# MX6ULL_DDR.net
KiCad netlist of a schematic drawn in Altium Designer
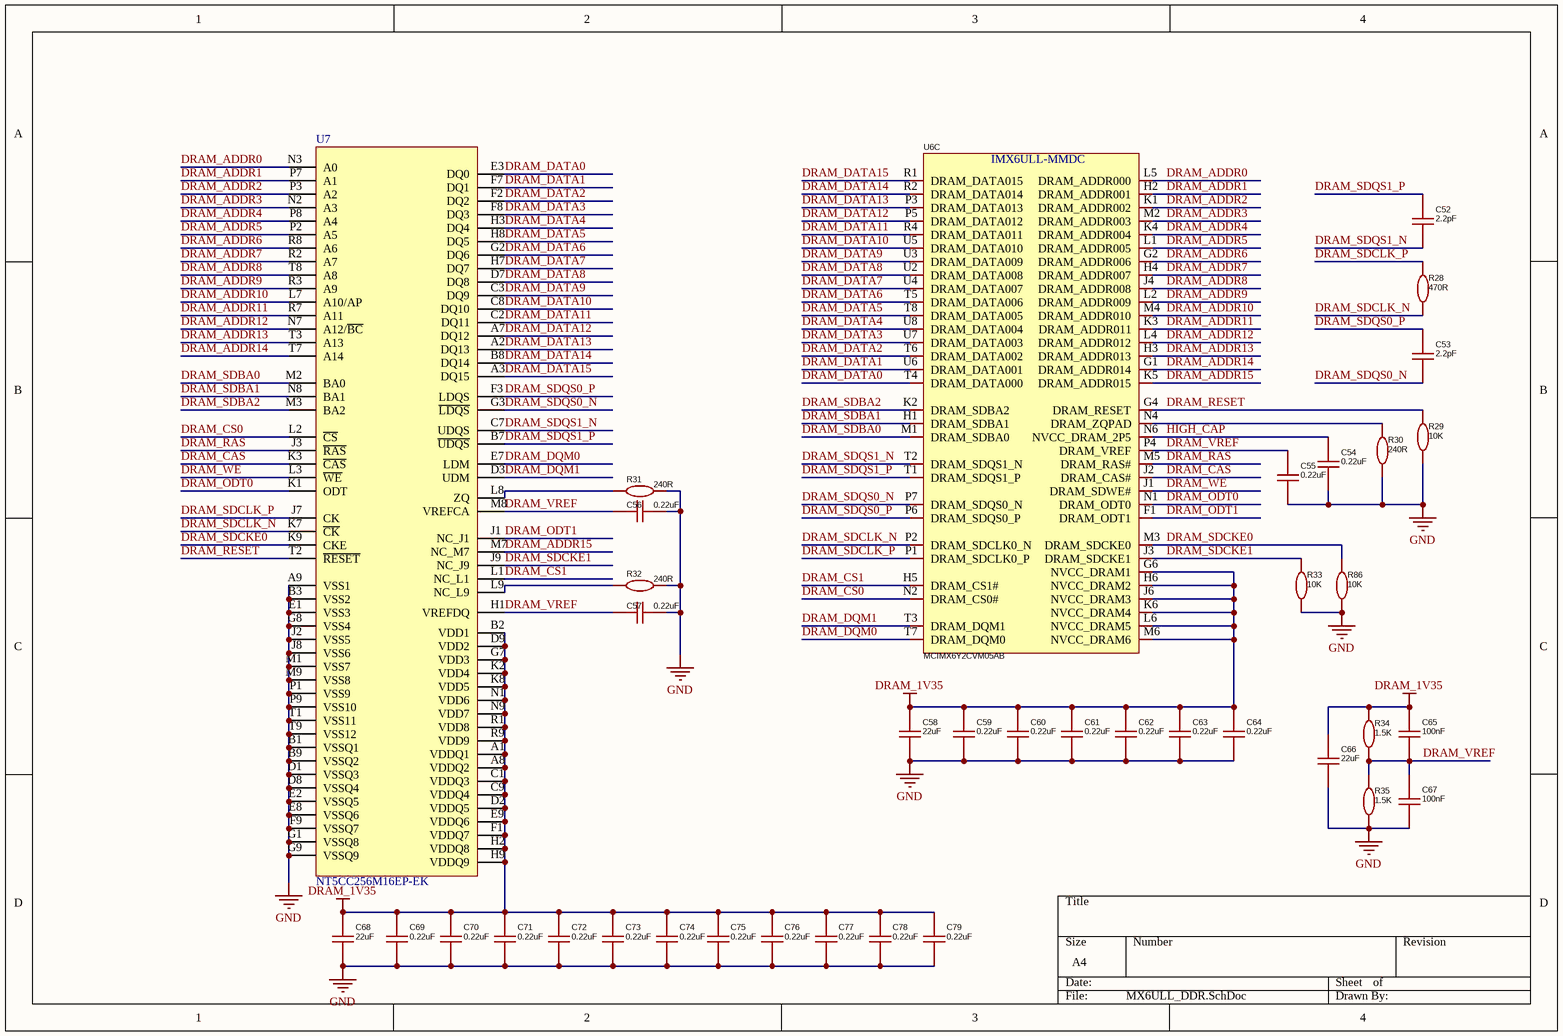
[diagram p0: MX6ULL_DDR.SchDoc]

(export (version "E")
  (design (tool "Eeschema 10.0.6"))
  (components
    (comp (ref "C52")
      (value "2.2pF")
      (footprint "PcbLib1:C0402")
      (description "容值:100nF;精度:±10%;额定电压:50V;材质(温度系数):X7R;")
      (fields
        (field (name "MANUFACTURER") "muRata(村田)")
        (field (name "MANUFACTURER PART") "GRM155R71H104KE14D")
      )
      (libsource (lib "Schlib1") (part "C0402"))
    )
    (comp (ref "C53")
      (value "2.2pF")
      (footprint "PcbLib1:C0402")
      (description "容值:100nF;精度:±10%;额定电压:50V;材质(温度系数):X7R;")
      (fields
        (field (name "MANUFACTURER") "muRata(村田)")
        (field (name "MANUFACTURER PART") "GRM155R71H104KE14D")
      )
      (libsource (lib "Schlib1") (part "C0402"))
    )
    (comp (ref "C54")
      (value "0.22uF")
      (footprint "PcbLib1:C0402")
      (description "容值:100nF;精度:±10%;额定电压:50V;材质(温度系数):X7R;")
      (fields
        (field (name "MANUFACTURER") "muRata(村田)")
        (field (name "MANUFACTURER PART") "GRM155R71H104KE14D")
      )
      (libsource (lib "Schlib1") (part "C0402"))
    )
    (comp (ref "C55")
      (value "0.22uF")
      (footprint "PcbLib1:C0402")
      (description "容值:100nF;精度:±10%;额定电压:50V;材质(温度系数):X7R;")
      (fields
        (field (name "MANUFACTURER") "muRata(村田)")
        (field (name "MANUFACTURER PART") "GRM155R71H104KE14D")
      )
      (libsource (lib "Schlib1") (part "C0402"))
    )
    (comp (ref "C56")
      (value "0.22uF")
      (footprint "PcbLib1:C0402")
      (description "容值:100nF;精度:±10%;额定电压:50V;材质(温度系数):X7R;")
      (fields
        (field (name "MANUFACTURER") "muRata(村田)")
        (field (name "MANUFACTURER PART") "GRM155R71H104KE14D")
      )
      (libsource (lib "Schlib1") (part "C0402"))
    )
    (comp (ref "C57")
      (value "0.22uF")
      (footprint "PcbLib1:C0402")
      (description "容值:100nF;精度:±10%;额定电压:50V;材质(温度系数):X7R;")
      (fields
        (field (name "MANUFACTURER") "muRata(村田)")
        (field (name "MANUFACTURER PART") "GRM155R71H104KE14D")
      )
      (libsource (lib "Schlib1") (part "C0402"))
    )
    (comp (ref "C58")
      (value "22uF")
      (footprint "PcbLib1:C0603")
      (description "容值:22uF;精度:±20%;额定电压:10V;材质(温度系数):X5R;")
      (fields
        (field (name "MANUFACTURER") "Chinocera(华瓷)")
        (field (name "MANUFACTURER PART") "HGC0603R5226M100NTHJ")
      )
      (libsource (lib "Schlib1") (part "C0603"))
    )
    (comp (ref "C59")
      (value "0.22uF")
      (footprint "PcbLib1:C0402")
      (description "容值:100nF;精度:±10%;额定电压:50V;材质(温度系数):X7R;")
      (fields
        (field (name "MANUFACTURER") "muRata(村田)")
        (field (name "MANUFACTURER PART") "GRM155R71H104KE14D")
      )
      (libsource (lib "Schlib1") (part "C0402"))
    )
    (comp (ref "C60")
      (value "0.22uF")
      (footprint "PcbLib1:C0402")
      (description "容值:100nF;精度:±10%;额定电压:50V;材质(温度系数):X7R;")
      (fields
        (field (name "MANUFACTURER") "muRata(村田)")
        (field (name "MANUFACTURER PART") "GRM155R71H104KE14D")
      )
      (libsource (lib "Schlib1") (part "C0402"))
    )
    (comp (ref "C61")
      (value "0.22uF")
      (footprint "PcbLib1:C0402")
      (description "容值:100nF;精度:±10%;额定电压:50V;材质(温度系数):X7R;")
      (fields
        (field (name "MANUFACTURER") "muRata(村田)")
        (field (name "MANUFACTURER PART") "GRM155R71H104KE14D")
      )
      (libsource (lib "Schlib1") (part "C0402"))
    )
    (comp (ref "C62")
      (value "0.22uF")
      (footprint "PcbLib1:C0402")
      (description "容值:100nF;精度:±10%;额定电压:50V;材质(温度系数):X7R;")
      (fields
        (field (name "MANUFACTURER") "muRata(村田)")
        (field (name "MANUFACTURER PART") "GRM155R71H104KE14D")
      )
      (libsource (lib "Schlib1") (part "C0402"))
    )
    (comp (ref "C63")
      (value "0.22uF")
      (footprint "PcbLib1:C0402")
      (description "容值:100nF;精度:±10%;额定电压:50V;材质(温度系数):X7R;")
      (fields
        (field (name "MANUFACTURER") "muRata(村田)")
        (field (name "MANUFACTURER PART") "GRM155R71H104KE14D")
      )
      (libsource (lib "Schlib1") (part "C0402"))
    )
    (comp (ref "C64")
      (value "0.22uF")
      (footprint "PcbLib1:C0402")
      (description "容值:100nF;精度:±10%;额定电压:50V;材质(温度系数):X7R;")
      (fields
        (field (name "MANUFACTURER") "muRata(村田)")
        (field (name "MANUFACTURER PART") "GRM155R71H104KE14D")
      )
      (libsource (lib "Schlib1") (part "C0402"))
    )
    (comp (ref "C65")
      (value "100nF")
      (footprint "PcbLib1:C0402")
      (description "容值:100nF;精度:±10%;额定电压:50V;材质(温度系数):X7R;")
      (fields
        (field (name "MANUFACTURER") "muRata(村田)")
        (field (name "MANUFACTURER PART") "GRM155R71H104KE14D")
      )
      (libsource (lib "Schlib1") (part "C0402"))
    )
    (comp (ref "C66")
      (value "22uF")
      (footprint "PcbLib1:C0603")
      (description "容值:22uF;精度:±20%;额定电压:10V;材质(温度系数):X5R;")
      (fields
        (field (name "MANUFACTURER") "Chinocera(华瓷)")
        (field (name "MANUFACTURER PART") "HGC0603R5226M100NTHJ")
      )
      (libsource (lib "Schlib1") (part "C0603"))
    )
    (comp (ref "C67")
      (value "100nF")
      (footprint "PcbLib1:C0402")
      (description "容值:100nF;精度:±10%;额定电压:50V;材质(温度系数):X7R;")
      (fields
        (field (name "MANUFACTURER") "muRata(村田)")
        (field (name "MANUFACTURER PART") "GRM155R71H104KE14D")
      )
      (libsource (lib "Schlib1") (part "C0402"))
    )
    (comp (ref "C68")
      (value "22uF")
      (footprint "PcbLib1:C0603")
      (description "容值:22uF;精度:±20%;额定电压:10V;材质(温度系数):X5R;")
      (fields
        (field (name "MANUFACTURER") "Chinocera(华瓷)")
        (field (name "MANUFACTURER PART") "HGC0603R5226M100NTHJ")
      )
      (libsource (lib "Schlib1") (part "C0603"))
    )
    (comp (ref "C69")
      (value "0.22uF")
      (footprint "PcbLib1:C0402")
      (description "容值:100nF;精度:±10%;额定电压:50V;材质(温度系数):X7R;")
      (fields
        (field (name "MANUFACTURER") "muRata(村田)")
        (field (name "MANUFACTURER PART") "GRM155R71H104KE14D")
      )
      (libsource (lib "Schlib1") (part "C0402"))
    )
    (comp (ref "C70")
      (value "0.22uF")
      (footprint "PcbLib1:C0402")
      (description "容值:100nF;精度:±10%;额定电压:50V;材质(温度系数):X7R;")
      (fields
        (field (name "MANUFACTURER") "muRata(村田)")
        (field (name "MANUFACTURER PART") "GRM155R71H104KE14D")
      )
      (libsource (lib "Schlib1") (part "C0402"))
    )
    (comp (ref "C71")
      (value "0.22uF")
      (footprint "PcbLib1:C0402")
      (description "容值:100nF;精度:±10%;额定电压:50V;材质(温度系数):X7R;")
      (fields
        (field (name "MANUFACTURER") "muRata(村田)")
        (field (name "MANUFACTURER PART") "GRM155R71H104KE14D")
      )
      (libsource (lib "Schlib1") (part "C0402"))
    )
    (comp (ref "C72")
      (value "0.22uF")
      (footprint "PcbLib1:C0402")
      (description "容值:100nF;精度:±10%;额定电压:50V;材质(温度系数):X7R;")
      (fields
        (field (name "MANUFACTURER") "muRata(村田)")
        (field (name "MANUFACTURER PART") "GRM155R71H104KE14D")
      )
      (libsource (lib "Schlib1") (part "C0402"))
    )
    (comp (ref "C73")
      (value "0.22uF")
      (footprint "PcbLib1:C0402")
      (description "容值:100nF;精度:±10%;额定电压:50V;材质(温度系数):X7R;")
      (fields
        (field (name "MANUFACTURER") "muRata(村田)")
        (field (name "MANUFACTURER PART") "GRM155R71H104KE14D")
      )
      (libsource (lib "Schlib1") (part "C0402"))
    )
    (comp (ref "C74")
      (value "0.22uF")
      (footprint "PcbLib1:C0402")
      (description "容值:100nF;精度:±10%;额定电压:50V;材质(温度系数):X7R;")
      (fields
        (field (name "MANUFACTURER") "muRata(村田)")
        (field (name "MANUFACTURER PART") "GRM155R71H104KE14D")
      )
      (libsource (lib "Schlib1") (part "C0402"))
    )
    (comp (ref "C75")
      (value "0.22uF")
      (footprint "PcbLib1:C0402")
      (description "容值:100nF;精度:±10%;额定电压:50V;材质(温度系数):X7R;")
      (fields
        (field (name "MANUFACTURER") "muRata(村田)")
        (field (name "MANUFACTURER PART") "GRM155R71H104KE14D")
      )
      (libsource (lib "Schlib1") (part "C0402"))
    )
    (comp (ref "C76")
      (value "0.22uF")
      (footprint "PcbLib1:C0402")
      (description "容值:100nF;精度:±10%;额定电压:50V;材质(温度系数):X7R;")
      (fields
        (field (name "MANUFACTURER") "muRata(村田)")
        (field (name "MANUFACTURER PART") "GRM155R71H104KE14D")
      )
      (libsource (lib "Schlib1") (part "C0402"))
    )
    (comp (ref "C77")
      (value "0.22uF")
      (footprint "PcbLib1:C0402")
      (description "容值:100nF;精度:±10%;额定电压:50V;材质(温度系数):X7R;")
      (fields
        (field (name "MANUFACTURER") "muRata(村田)")
        (field (name "MANUFACTURER PART") "GRM155R71H104KE14D")
      )
      (libsource (lib "Schlib1") (part "C0402"))
    )
    (comp (ref "C78")
      (value "0.22uF")
      (footprint "PcbLib1:C0402")
      (description "容值:100nF;精度:±10%;额定电压:50V;材质(温度系数):X7R;")
      (fields
        (field (name "MANUFACTURER") "muRata(村田)")
        (field (name "MANUFACTURER PART") "GRM155R71H104KE14D")
      )
      (libsource (lib "Schlib1") (part "C0402"))
    )
    (comp (ref "C79")
      (value "0.22uF")
      (footprint "PcbLib1:C0402")
      (description "容值:100nF;精度:±10%;额定电压:50V;材质(温度系数):X7R;")
      (fields
        (field (name "MANUFACTURER") "muRata(村田)")
        (field (name "MANUFACTURER PART") "GRM155R71H104KE14D")
      )
      (libsource (lib "Schlib1") (part "C0402"))
    )
    (comp (ref "R28")
      (value "470R")
      (footprint "PcbLib1:R0402")
      (description "电阻类型:厚膜电阻;阻值:1kΩ;精度:±1%;功率:62.5mW;最大工作电压:50V;温度系数:±100ppm/℃;")
      (fields
        (field (name "MANUFACTURER") "UNI-ROYAL(厚声)")
        (field (name "MANUFACTURER PART") "0402WGF1001TCE")
      )
      (libsource (lib "Schlib1") (part "R0402"))
    )
    (comp (ref "R29")
      (value "10K")
      (footprint "PcbLib1:R0402")
      (description "电阻类型:厚膜电阻;阻值:1kΩ;精度:±1%;功率:62.5mW;最大工作电压:50V;温度系数:±100ppm/℃;")
      (fields
        (field (name "MANUFACTURER") "UNI-ROYAL(厚声)")
        (field (name "MANUFACTURER PART") "0402WGF1001TCE")
      )
      (libsource (lib "Schlib1") (part "R0402"))
    )
    (comp (ref "R30")
      (value "240R")
      (footprint "PcbLib1:R0402")
      (description "电阻类型:厚膜电阻;阻值:1kΩ;精度:±1%;功率:62.5mW;最大工作电压:50V;温度系数:±100ppm/℃;")
      (fields
        (field (name "MANUFACTURER") "UNI-ROYAL(厚声)")
        (field (name "MANUFACTURER PART") "0402WGF1001TCE")
      )
      (libsource (lib "Schlib1") (part "R0402"))
    )
    (comp (ref "R31")
      (value "240R")
      (footprint "PcbLib1:R0402")
      (description "电阻类型:厚膜电阻;阻值:1kΩ;精度:±1%;功率:62.5mW;最大工作电压:50V;温度系数:±100ppm/℃;")
      (fields
        (field (name "MANUFACTURER") "UNI-ROYAL(厚声)")
        (field (name "MANUFACTURER PART") "0402WGF1001TCE")
      )
      (libsource (lib "Schlib1") (part "R0402"))
    )
    (comp (ref "R32")
      (value "240R")
      (footprint "PcbLib1:R0402")
      (description "电阻类型:厚膜电阻;阻值:1kΩ;精度:±1%;功率:62.5mW;最大工作电压:50V;温度系数:±100ppm/℃;")
      (fields
        (field (name "MANUFACTURER") "UNI-ROYAL(厚声)")
        (field (name "MANUFACTURER PART") "0402WGF1001TCE")
      )
      (libsource (lib "Schlib1") (part "R0402"))
    )
    (comp (ref "R33")
      (value "10K")
      (footprint "PcbLib1:R0402")
      (description "电阻类型:厚膜电阻;阻值:1kΩ;精度:±1%;功率:62.5mW;最大工作电压:50V;温度系数:±100ppm/℃;")
      (fields
        (field (name "MANUFACTURER") "UNI-ROYAL(厚声)")
        (field (name "MANUFACTURER PART") "0402WGF1001TCE")
      )
      (libsource (lib "Schlib1") (part "R0402"))
    )
    (comp (ref "R34")
      (value "1.5K")
      (footprint "PcbLib1:R0402")
      (description "电阻类型:厚膜电阻;阻值:1kΩ;精度:±1%;功率:62.5mW;最大工作电压:50V;温度系数:±100ppm/℃;")
      (fields
        (field (name "MANUFACTURER") "UNI-ROYAL(厚声)")
        (field (name "MANUFACTURER PART") "0402WGF1001TCE")
      )
      (libsource (lib "Schlib1") (part "R0402"))
    )
    (comp (ref "R35")
      (value "1.5K")
      (footprint "PcbLib1:R0402")
      (description "电阻类型:厚膜电阻;阻值:1kΩ;精度:±1%;功率:62.5mW;最大工作电压:50V;温度系数:±100ppm/℃;")
      (fields
        (field (name "MANUFACTURER") "UNI-ROYAL(厚声)")
        (field (name "MANUFACTURER PART") "0402WGF1001TCE")
      )
      (libsource (lib "Schlib1") (part "R0402"))
    )
    (comp (ref "R86")
      (value "10K")
      (footprint "PcbLib1:R0402")
      (description "电阻类型:厚膜电阻;阻值:1kΩ;精度:±1%;功率:62.5mW;最大工作电压:50V;温度系数:±100ppm/℃;")
      (fields
        (field (name "MANUFACTURER") "UNI-ROYAL(厚声)")
        (field (name "MANUFACTURER PART") "0402WGF1001TCE")
      )
      (libsource (lib "Schlib1") (part "R0402"))
    )
    (comp (ref "U6")
      (value "MCIMX6Y2CVM05AB")
      (footprint "PcbLib1:BGA-289_L14.0-W14.0-R17-C17-P0.80-BL")
      (description "CPU内核:ARM-A系列;RAM总容量:128KB;GPIO端口数量:-;工作电压范围:-;CPU最大主频:528MHz;程序存储器类型:-;应用领域:-;")
      (fields (field (name "MANUFACTURER") "NXP(恩智浦)"))
      (libsource (lib "Schlib1") (part "MCIMX6Y2CVM05AB"))
    )
    (comp (ref "U7")
      (value "NT5CC256M16EP-EK")
      (footprint "PcbLib1:TFBGA-96_L13.0-W8.0-R16-C6-P0.80-TL")
      (libsource (lib "Schlib1") (part "MT41K256M16TW"))
    )
  )
  (nets
    (net (code "1") (name "/DRAM_ADDR0") (class "Default")
      (node (ref "U6") (pin "L5") (pinfunction "DRAM_ADDR000_L5") (pintype "passive"))
      (node (ref "U7") (pin "N3") (pinfunction "A0_N3") (pintype "passive"))
    )
    (net (code "2") (name "/DRAM_ADDR1") (class "Default")
      (node (ref "U6") (pin "H2") (pinfunction "DRAM_ADDR001_H2") (pintype "passive"))
      (node (ref "U7") (pin "P7") (pinfunction "A1_P7") (pintype "passive"))
    )
    (net (code "3") (name "/DRAM_ADDR2") (class "Default")
      (node (ref "U6") (pin "K1") (pinfunction "DRAM_ADDR002_K1") (pintype "passive"))
      (node (ref "U7") (pin "P3") (pinfunction "A2_P3") (pintype "passive"))
    )
    (net (code "4") (name "/DRAM_ADDR3") (class "Default")
      (node (ref "U6") (pin "M2") (pinfunction "DRAM_ADDR003_M2") (pintype "passive"))
      (node (ref "U7") (pin "N2") (pinfunction "A3_N2") (pintype "passive"))
    )
    (net (code "5") (name "/DRAM_ADDR4") (class "Default")
      (node (ref "U6") (pin "K4") (pinfunction "DRAM_ADDR004_K4") (pintype "passive"))
      (node (ref "U7") (pin "P8") (pinfunction "A4_P8") (pintype "passive"))
    )
    (net (code "6") (name "/DRAM_ADDR5") (class "Default")
      (node (ref "U6") (pin "L1") (pinfunction "DRAM_ADDR005_L1") (pintype "passive"))
      (node (ref "U7") (pin "P2") (pinfunction "A5_P2") (pintype "passive"))
    )
    (net (code "7") (name "/DRAM_ADDR6") (class "Default")
      (node (ref "U6") (pin "G2") (pinfunction "DRAM_ADDR006_G2") (pintype "passive"))
      (node (ref "U7") (pin "R8") (pinfunction "A6_R8") (pintype "passive"))
    )
    (net (code "8") (name "/DRAM_ADDR7") (class "Default")
      (node (ref "U6") (pin "H4") (pinfunction "DRAM_ADDR007_H4") (pintype "passive"))
      (node (ref "U7") (pin "R2") (pinfunction "A7_R2") (pintype "passive"))
    )
    (net (code "9") (name "/DRAM_ADDR8") (class "Default")
      (node (ref "U6") (pin "J4") (pinfunction "DRAM_ADDR008_J4") (pintype "passive"))
      (node (ref "U7") (pin "T8") (pinfunction "A8_T8") (pintype "passive"))
    )
    (net (code "10") (name "/DRAM_ADDR9") (class "Default")
      (node (ref "U6") (pin "L2") (pinfunction "DRAM_ADDR009_L2") (pintype "passive"))
      (node (ref "U7") (pin "R3") (pinfunction "A9_R3") (pintype "passive"))
    )
    (net (code "11") (name "/DRAM_ADDR10") (class "Default")
      (node (ref "U6") (pin "M4") (pinfunction "DRAM_ADDR010_M4") (pintype "passive"))
      (node (ref "U7") (pin "L7") (pinfunction "A10/AP_L7") (pintype "passive"))
    )
    (net (code "12") (name "/DRAM_ADDR11") (class "Default")
      (node (ref "U6") (pin "K3") (pinfunction "DRAM_ADDR011_K3") (pintype "passive"))
      (node (ref "U7") (pin "R7") (pinfunction "A11_R7") (pintype "passive"))
    )
    (net (code "13") (name "/DRAM_ADDR12") (class "Default")
      (node (ref "U6") (pin "L4") (pinfunction "DRAM_ADDR012_L4") (pintype "passive"))
      (node (ref "U7") (pin "N7") (pinfunction "A12/~{BC}_N7") (pintype "passive"))
    )
    (net (code "14") (name "/DRAM_ADDR13") (class "Default")
      (node (ref "U6") (pin "H3") (pinfunction "DRAM_ADDR013_H3") (pintype "passive"))
      (node (ref "U7") (pin "T3") (pinfunction "A13_T3") (pintype "passive"))
    )
    (net (code "15") (name "/DRAM_ADDR14") (class "Default")
      (node (ref "U6") (pin "G1") (pinfunction "DRAM_ADDR014_G1") (pintype "passive"))
      (node (ref "U7") (pin "T7") (pinfunction "A14_T7") (pintype "passive"))
    )
    (net (code "16") (name "/DRAM_ADDR15") (class "Default")
      (node (ref "U6") (pin "K5") (pinfunction "DRAM_ADDR015_K5") (pintype "passive"))
      (node (ref "U7") (pin "M7") (pinfunction "NC_M7_M7") (pintype "passive"))
    )
    (net (code "17") (name "/DRAM_CAS") (class "Default")
      (node (ref "U6") (pin "J2") (pinfunction "DRAM_CAS#_J2") (pintype "passive"))
      (node (ref "U7") (pin "K3") (pinfunction "~{CAS}_K3") (pintype "passive"))
    )
    (net (code "18") (name "/DRAM_CS0") (class "Default")
      (node (ref "U6") (pin "N2") (pinfunction "DRAM_CS0#_N2") (pintype "passive"))
      (node (ref "U7") (pin "L2") (pinfunction "~{CS}_L2") (pintype "passive"))
    )
    (net (code "19") (name "/DRAM_CS1") (class "Default")
      (node (ref "U6") (pin "H5") (pinfunction "DRAM_CS1#_H5") (pintype "passive"))
      (node (ref "U7") (pin "L1") (pinfunction "NC_L1_L1") (pintype "passive"))
    )
    (net (code "20") (name "/DRAM_DATA0") (class "Default")
      (node (ref "U6") (pin "T4") (pinfunction "DRAM_DATA000_T4") (pintype "passive"))
      (node (ref "U7") (pin "E3") (pinfunction "DQ0_E3") (pintype "passive"))
    )
    (net (code "21") (name "/DRAM_DATA1") (class "Default")
      (node (ref "U6") (pin "U6") (pinfunction "DRAM_DATA001_U6") (pintype "passive"))
      (node (ref "U7") (pin "F7") (pinfunction "DQ1_F7") (pintype "passive"))
    )
    (net (code "22") (name "/DRAM_DATA2") (class "Default")
      (node (ref "U6") (pin "T6") (pinfunction "DRAM_DATA002_T6") (pintype "passive"))
      (node (ref "U7") (pin "F2") (pinfunction "DQ2_F2") (pintype "passive"))
    )
    (net (code "23") (name "/DRAM_DATA3") (class "Default")
      (node (ref "U6") (pin "U7") (pinfunction "DRAM_DATA003_U7") (pintype "passive"))
      (node (ref "U7") (pin "F8") (pinfunction "DQ3_F8") (pintype "passive"))
    )
    (net (code "24") (name "/DRAM_DATA4") (class "Default")
      (node (ref "U6") (pin "U8") (pinfunction "DRAM_DATA004_U8") (pintype "passive"))
      (node (ref "U7") (pin "H3") (pinfunction "DQ4_H3") (pintype "passive"))
    )
    (net (code "25") (name "/DRAM_DATA5") (class "Default")
      (node (ref "U6") (pin "T8") (pinfunction "DRAM_DATA005_T8") (pintype "passive"))
      (node (ref "U7") (pin "H8") (pinfunction "DQ5_H8") (pintype "passive"))
    )
    (net (code "26") (name "/DRAM_DATA6") (class "Default")
      (node (ref "U6") (pin "T5") (pinfunction "DRAM_DATA006_T5") (pintype "passive"))
      (node (ref "U7") (pin "G2") (pinfunction "DQ6_G2") (pintype "passive"))
    )
    (net (code "27") (name "/DRAM_DATA7") (class "Default")
      (node (ref "U6") (pin "U4") (pinfunction "DRAM_DATA007_U4") (pintype "passive"))
      (node (ref "U7") (pin "H7") (pinfunction "DQ7_H7") (pintype "passive"))
    )
    (net (code "28") (name "/DRAM_DATA8") (class "Default")
      (node (ref "U6") (pin "U2") (pinfunction "DRAM_DATA008_U2") (pintype "passive"))
      (node (ref "U7") (pin "D7") (pinfunction "DQ8_D7") (pintype "passive"))
    )
    (net (code "29") (name "/DRAM_DATA9") (class "Default")
      (node (ref "U6") (pin "U3") (pinfunction "DRAM_DATA009_U3") (pintype "passive"))
      (node (ref "U7") (pin "C3") (pinfunction "DQ9_C3") (pintype "passive"))
    )
    (net (code "30") (name "/DRAM_DATA10") (class "Default")
      (node (ref "U6") (pin "U5") (pinfunction "DRAM_DATA010_U5") (pintype "passive"))
      (node (ref "U7") (pin "C8") (pinfunction "DQ10_C8") (pintype "passive"))
    )
    (net (code "31") (name "/DRAM_DATA11") (class "Default")
      (node (ref "U6") (pin "R4") (pinfunction "DRAM_DATA011_R4") (pintype "passive"))
      (node (ref "U7") (pin "C2") (pinfunction "DQ11_C2") (pintype "passive"))
    )
    (net (code "32") (name "/DRAM_DATA12") (class "Default")
      (node (ref "U6") (pin "P5") (pinfunction "DRAM_DATA012_P5") (pintype "passive"))
      (node (ref "U7") (pin "A7") (pinfunction "DQ12_A7") (pintype "passive"))
    )
    (net (code "33") (name "/DRAM_DATA13") (class "Default")
      (node (ref "U6") (pin "P3") (pinfunction "DRAM_DATA013_P3") (pintype "passive"))
      (node (ref "U7") (pin "A2") (pinfunction "DQ13_A2") (pintype "passive"))
    )
    (net (code "34") (name "/DRAM_DATA14") (class "Default")
      (node (ref "U6") (pin "R2") (pinfunction "DRAM_DATA014_R2") (pintype "passive"))
      (node (ref "U7") (pin "B8") (pinfunction "DQ14_B8") (pintype "passive"))
    )
    (net (code "35") (name "/DRAM_DATA15") (class "Default")
      (node (ref "U6") (pin "R1") (pinfunction "DRAM_DATA015_R1") (pintype "passive"))
      (node (ref "U7") (pin "A3") (pinfunction "DQ15_A3") (pintype "passive"))
    )
    (net (code "36") (name "/DRAM_DQM0") (class "Default")
      (node (ref "U6") (pin "T7") (pinfunction "DRAM_DQM0_T7") (pintype "passive"))
      (node (ref "U7") (pin "E7") (pinfunction "LDM_E7") (pintype "passive"))
    )
    (net (code "37") (name "/DRAM_DQM1") (class "Default")
      (node (ref "U6") (pin "T3") (pinfunction "DRAM_DQM1_T3") (pintype "passive"))
      (node (ref "U7") (pin "D3") (pinfunction "UDM_D3") (pintype "passive"))
    )
    (net (code "38") (name "/DRAM_ODT0") (class "Default")
      (node (ref "U6") (pin "N1") (pinfunction "DRAM_ODT0_N1") (pintype "passive"))
      (node (ref "U7") (pin "K1") (pinfunction "ODT_K1") (pintype "passive"))
    )
    (net (code "39") (name "/DRAM_ODT1") (class "Default")
      (node (ref "U6") (pin "F1") (pinfunction "DRAM_ODT1_F1") (pintype "passive"))
      (node (ref "U7") (pin "J1") (pinfunction "NC_J1_J1") (pintype "passive"))
    )
    (net (code "40") (name "/DRAM_RAS") (class "Default")
      (node (ref "U6") (pin "M5") (pinfunction "DRAM_RAS#_M5") (pintype "passive"))
      (node (ref "U7") (pin "J3") (pinfunction "~{RAS}_J3") (pintype "passive"))
    )
    (net (code "41") (name "/DRAM_RESET") (class "Default")
      (node (ref "R29") (pin "2") (pinfunction "2_2") (pintype "passive"))
      (node (ref "U6") (pin "G4") (pinfunction "DRAM_RESET_G4") (pintype "passive"))
      (node (ref "U7") (pin "T2") (pinfunction "~{RESET}_T2") (pintype "passive"))
    )
    (net (code "42") (name "/DRAM_SDBA0") (class "Default")
      (node (ref "U6") (pin "M1") (pinfunction "DRAM_SDBA0_M1") (pintype "passive"))
      (node (ref "U7") (pin "M2") (pinfunction "BA0_M2") (pintype "passive"))
    )
    (net (code "43") (name "/DRAM_SDBA1") (class "Default")
      (node (ref "U6") (pin "H1") (pinfunction "DRAM_SDBA1_H1") (pintype "passive"))
      (node (ref "U7") (pin "N8") (pinfunction "BA1_N8") (pintype "passive"))
    )
    (net (code "44") (name "/DRAM_SDBA2") (class "Default")
      (node (ref "U6") (pin "K2") (pinfunction "DRAM_SDBA2_K2") (pintype "passive"))
      (node (ref "U7") (pin "M3") (pinfunction "BA2_M3") (pintype "passive"))
    )
    (net (code "45") (name "/DRAM_SDCKE0") (class "Default")
      (node (ref "R86") (pin "2") (pinfunction "2_2") (pintype "passive"))
      (node (ref "U6") (pin "M3") (pinfunction "DRAM_SDCKE0_M3") (pintype "passive"))
      (node (ref "U7") (pin "K9") (pinfunction "CKE_K9") (pintype "passive"))
    )
    (net (code "46") (name "/DRAM_SDCKE1") (class "Default")
      (node (ref "R33") (pin "2") (pinfunction "2_2") (pintype "passive"))
      (node (ref "U6") (pin "J3") (pinfunction "DRAM_SDCKE1_J3") (pintype "passive"))
      (node (ref "U7") (pin "J9") (pinfunction "NC_J9_J9") (pintype "passive"))
    )
    (net (code "47") (name "/DRAM_SDCLK_N") (class "Default")
      (node (ref "R28") (pin "1") (pinfunction "1_1") (pintype "passive"))
      (node (ref "U6") (pin "P2") (pinfunction "DRAM_SDCLK0_N_P2") (pintype "passive"))
      (node (ref "U7") (pin "K7") (pinfunction "~{CK}_K7") (pintype "passive"))
    )
    (net (code "48") (name "/DRAM_SDCLK_P") (class "Default")
      (node (ref "R28") (pin "2") (pinfunction "2_2") (pintype "passive"))
      (node (ref "U6") (pin "P1") (pinfunction "DRAM_SDCLK0_P_P1") (pintype "passive"))
      (node (ref "U7") (pin "J7") (pinfunction "CK_J7") (pintype "passive"))
    )
    (net (code "49") (name "/DRAM_SDQS0_N") (class "Default")
      (node (ref "C53") (pin "1") (pinfunction "1_1") (pintype "passive"))
      (node (ref "U6") (pin "P7") (pinfunction "DRAM_SDQS0_N_P7") (pintype "passive"))
      (node (ref "U7") (pin "G3") (pinfunction "~{LDQS}_G3") (pintype "passive"))
    )
    (net (code "50") (name "/DRAM_SDQS0_P") (class "Default")
      (node (ref "C53") (pin "2") (pinfunction "2_2") (pintype "passive"))
      (node (ref "U6") (pin "P6") (pinfunction "DRAM_SDQS0_P_P6") (pintype "passive"))
      (node (ref "U7") (pin "F3") (pinfunction "LDQS_F3") (pintype "passive"))
    )
    (net (code "51") (name "/DRAM_SDQS1_N") (class "Default")
      (node (ref "C52") (pin "1") (pinfunction "1_1") (pintype "passive"))
      (node (ref "U6") (pin "T2") (pinfunction "DRAM_SDQS1_N_T2") (pintype "passive"))
      (node (ref "U7") (pin "C7") (pinfunction "UDQS_C7") (pintype "passive"))
    )
    (net (code "52") (name "/DRAM_SDQS1_P") (class "Default")
      (node (ref "C52") (pin "2") (pinfunction "2_2") (pintype "passive"))
      (node (ref "U6") (pin "T1") (pinfunction "DRAM_SDQS1_P_T1") (pintype "passive"))
      (node (ref "U7") (pin "B7") (pinfunction "~{UDQS}_B7") (pintype "passive"))
    )
    (net (code "53") (name "/DRAM_VREF") (class "Default")
      (node (ref "C55") (pin "2") (pinfunction "2_2") (pintype "passive"))
      (node (ref "C56") (pin "2") (pinfunction "2_2") (pintype "passive"))
      (node (ref "C57") (pin "2") (pinfunction "2_2") (pintype "passive"))
      (node (ref "C65") (pin "1") (pinfunction "1_1") (pintype "passive"))
      (node (ref "C67") (pin "2") (pinfunction "2_2") (pintype "passive"))
      (node (ref "R34") (pin "1") (pinfunction "1_1") (pintype "passive"))
      (node (ref "R35") (pin "2") (pinfunction "2_2") (pintype "passive"))
      (node (ref "U6") (pin "P4") (pinfunction "DRAM_VREF_P4") (pintype "passive"))
      (node (ref "U7") (pin "H1") (pinfunction "VREFDQ_H1") (pintype "passive"))
      (node (ref "U7") (pin "M8") (pinfunction "VREFCA_M8") (pintype "passive"))
    )
    (net (code "54") (name "/DRAM_WE") (class "Default")
      (node (ref "U6") (pin "J1") (pinfunction "DRAM_SDWE#_J1") (pintype "passive"))
      (node (ref "U7") (pin "L3") (pinfunction "~{WE}_L3") (pintype "passive"))
    )
    (net (code "55") (name "/HIGH_CAP") (class "Default")
      (node (ref "C54") (pin "2") (pinfunction "2_2") (pintype "passive"))
      (node (ref "U6") (pin "N6") (pinfunction "NVCC_DRAM_2P5_N6") (pintype "passive"))
    )
    (net (code "56") (name "DRAM_1V35") (class "Default")
      (node (ref "C58") (pin "2") (pinfunction "2_2") (pintype "passive"))
      (node (ref "C59") (pin "2") (pinfunction "2_2") (pintype "passive"))
      (node (ref "C60") (pin "2") (pinfunction "2_2") (pintype "passive"))
      (node (ref "C61") (pin "2") (pinfunction "2_2") (pintype "passive"))
      (node (ref "C62") (pin "2") (pinfunction "2_2") (pintype "passive"))
      (node (ref "C63") (pin "2") (pinfunction "2_2") (pintype "passive"))
      (node (ref "C64") (pin "2") (pinfunction "2_2") (pintype "passive"))
      (node (ref "C65") (pin "2") (pinfunction "2_2") (pintype "passive"))
      (node (ref "C66") (pin "2") (pinfunction "2_2") (pintype "passive"))
      (node (ref "C68") (pin "2") (pinfunction "2_2") (pintype "passive"))
      (node (ref "C69") (pin "2") (pinfunction "2_2") (pintype "passive"))
      (node (ref "C70") (pin "2") (pinfunction "2_2") (pintype "passive"))
      (node (ref "C71") (pin "2") (pinfunction "2_2") (pintype "passive"))
      (node (ref "C72") (pin "2") (pinfunction "2_2") (pintype "passive"))
      (node (ref "C73") (pin "2") (pinfunction "2_2") (pintype "passive"))
      (node (ref "C74") (pin "2") (pinfunction "2_2") (pintype "passive"))
      (node (ref "C75") (pin "2") (pinfunction "2_2") (pintype "passive"))
      (node (ref "C76") (pin "2") (pinfunction "2_2") (pintype "passive"))
      (node (ref "C77") (pin "2") (pinfunction "2_2") (pintype "passive"))
      (node (ref "C78") (pin "2") (pinfunction "2_2") (pintype "passive"))
      (node (ref "C79") (pin "2") (pinfunction "2_2") (pintype "passive"))
      (node (ref "R34") (pin "2") (pinfunction "2_2") (pintype "passive"))
      (node (ref "U6") (pin "G6") (pinfunction "NVCC_DRAM1_G6") (pintype "passive"))
      (node (ref "U6") (pin "H6") (pinfunction "NVCC_DRAM2_H6") (pintype "passive"))
      (node (ref "U6") (pin "J6") (pinfunction "NVCC_DRAM3_J6") (pintype "passive"))
      (node (ref "U6") (pin "K6") (pinfunction "NVCC_DRAM4_K6") (pintype "passive"))
      (node (ref "U6") (pin "L6") (pinfunction "NVCC_DRAM5_L6") (pintype "passive"))
      (node (ref "U6") (pin "M6") (pinfunction "NVCC_DRAM6_M6") (pintype "passive"))
      (node (ref "U7") (pin "A1") (pinfunction "VDDQ1_A1") (pintype "passive"))
      (node (ref "U7") (pin "A8") (pinfunction "VDDQ2_A8") (pintype "passive"))
      (node (ref "U7") (pin "B2") (pinfunction "VDD1_B2") (pintype "passive"))
      (node (ref "U7") (pin "C1") (pinfunction "VDDQ3_C1") (pintype "passive"))
      (node (ref "U7") (pin "C9") (pinfunction "VDDQ4_C9") (pintype "passive"))
      (node (ref "U7") (pin "D2") (pinfunction "VDDQ5_D2") (pintype "passive"))
      (node (ref "U7") (pin "D9") (pinfunction "VDD2_D9") (pintype "passive"))
      (node (ref "U7") (pin "E9") (pinfunction "VDDQ6_E9") (pintype "passive"))
      (node (ref "U7") (pin "F1") (pinfunction "VDDQ7_F1") (pintype "passive"))
      (node (ref "U7") (pin "G7") (pinfunction "VDD3_G7") (pintype "passive"))
      (node (ref "U7") (pin "H2") (pinfunction "VDDQ8_H2") (pintype "passive"))
      (node (ref "U7") (pin "H9") (pinfunction "VDDQ9_H9") (pintype "passive"))
      (node (ref "U7") (pin "K2") (pinfunction "VDD4_K2") (pintype "passive"))
      (node (ref "U7") (pin "K8") (pinfunction "VDD5_K8") (pintype "passive"))
      (node (ref "U7") (pin "N1") (pinfunction "VDD6_N1") (pintype "passive"))
      (node (ref "U7") (pin "N9") (pinfunction "VDD7_N9") (pintype "passive"))
      (node (ref "U7") (pin "R1") (pinfunction "VDD8_R1") (pintype "passive"))
      (node (ref "U7") (pin "R9") (pinfunction "VDD9_R9") (pintype "passive"))
    )
    (net (code "57") (name "GND") (class "Default")
      (node (ref "C54") (pin "1") (pinfunction "1_1") (pintype "passive"))
      (node (ref "C55") (pin "1") (pinfunction "1_1") (pintype "passive"))
      (node (ref "C56") (pin "1") (pinfunction "1_1") (pintype "passive"))
      (node (ref "C57") (pin "1") (pinfunction "1_1") (pintype "passive"))
      (node (ref "C58") (pin "1") (pinfunction "1_1") (pintype "passive"))
      (node (ref "C59") (pin "1") (pinfunction "1_1") (pintype "passive"))
      (node (ref "C60") (pin "1") (pinfunction "1_1") (pintype "passive"))
      (node (ref "C61") (pin "1") (pinfunction "1_1") (pintype "passive"))
      (node (ref "C62") (pin "1") (pinfunction "1_1") (pintype "passive"))
      (node (ref "C63") (pin "1") (pinfunction "1_1") (pintype "passive"))
      (node (ref "C64") (pin "1") (pinfunction "1_1") (pintype "passive"))
      (node (ref "C66") (pin "1") (pinfunction "1_1") (pintype "passive"))
      (node (ref "C67") (pin "1") (pinfunction "1_1") (pintype "passive"))
      (node (ref "C68") (pin "1") (pinfunction "1_1") (pintype "passive"))
      (node (ref "C69") (pin "1") (pinfunction "1_1") (pintype "passive"))
      (node (ref "C70") (pin "1") (pinfunction "1_1") (pintype "passive"))
      (node (ref "C71") (pin "1") (pinfunction "1_1") (pintype "passive"))
      (node (ref "C72") (pin "1") (pinfunction "1_1") (pintype "passive"))
      (node (ref "C73") (pin "1") (pinfunction "1_1") (pintype "passive"))
      (node (ref "C74") (pin "1") (pinfunction "1_1") (pintype "passive"))
      (node (ref "C75") (pin "1") (pinfunction "1_1") (pintype "passive"))
      (node (ref "C76") (pin "1") (pinfunction "1_1") (pintype "passive"))
      (node (ref "C77") (pin "1") (pinfunction "1_1") (pintype "passive"))
      (node (ref "C78") (pin "1") (pinfunction "1_1") (pintype "passive"))
      (node (ref "C79") (pin "1") (pinfunction "1_1") (pintype "passive"))
      (node (ref "R29") (pin "1") (pinfunction "1_1") (pintype "passive"))
      (node (ref "R30") (pin "1") (pinfunction "1_1") (pintype "passive"))
      (node (ref "R31") (pin "1") (pinfunction "1_1") (pintype "passive"))
      (node (ref "R32") (pin "1") (pinfunction "1_1") (pintype "passive"))
      (node (ref "R33") (pin "1") (pinfunction "1_1") (pintype "passive"))
      (node (ref "R35") (pin "1") (pinfunction "1_1") (pintype "passive"))
      (node (ref "R86") (pin "1") (pinfunction "1_1") (pintype "passive"))
      (node (ref "U7") (pin "A9") (pinfunction "VSS1_A9") (pintype "passive"))
      (node (ref "U7") (pin "B1") (pinfunction "VSSQ1_B1") (pintype "passive"))
      (node (ref "U7") (pin "B3") (pinfunction "VSS2_B3") (pintype "passive"))
      (node (ref "U7") (pin "B9") (pinfunction "VSSQ2_B9") (pintype "passive"))
      (node (ref "U7") (pin "D1") (pinfunction "VSSQ3_D1") (pintype "passive"))
      (node (ref "U7") (pin "D8") (pinfunction "VSSQ4_D8") (pintype "passive"))
      (node (ref "U7") (pin "E1") (pinfunction "VSS3_E1") (pintype "passive"))
      (node (ref "U7") (pin "E2") (pinfunction "VSSQ5_E2") (pintype "passive"))
      (node (ref "U7") (pin "E8") (pinfunction "VSSQ6_E8") (pintype "passive"))
      (node (ref "U7") (pin "F9") (pinfunction "VSSQ7_F9") (pintype "passive"))
      (node (ref "U7") (pin "G1") (pinfunction "VSSQ8_G1") (pintype "passive"))
      (node (ref "U7") (pin "G8") (pinfunction "VSS4_G8") (pintype "passive"))
      (node (ref "U7") (pin "G9") (pinfunction "VSSQ9_G9") (pintype "passive"))
      (node (ref "U7") (pin "J2") (pinfunction "VSS5_J2") (pintype "passive"))
      (node (ref "U7") (pin "J8") (pinfunction "VSS6_J8") (pintype "passive"))
      (node (ref "U7") (pin "M1") (pinfunction "VSS7_M1") (pintype "passive"))
      (node (ref "U7") (pin "M9") (pinfunction "VSS8_M9") (pintype "passive"))
      (node (ref "U7") (pin "P1") (pinfunction "VSS9_P1") (pintype "passive"))
      (node (ref "U7") (pin "P9") (pinfunction "VSS10_P9") (pintype "passive"))
      (node (ref "U7") (pin "T1") (pinfunction "VSS11_T1") (pintype "passive"))
      (node (ref "U7") (pin "T9") (pinfunction "VSS12_T9") (pintype "passive"))
    )
    (net (code "58") (name "Net-(U6C-DRAM_ZQPAD)") (class "Default")
      (node (ref "R30") (pin "2") (pinfunction "2_2") (pintype "passive"))
      (node (ref "U6") (pin "N4") (pinfunction "DRAM_ZQPAD_N4") (pintype "passive"))
    )
    (net (code "59") (name "Net-(U7-NC_L9)") (class "Default")
      (node (ref "R32") (pin "2") (pinfunction "2_2") (pintype "passive"))
      (node (ref "U7") (pin "L9") (pinfunction "NC_L9_L9") (pintype "passive"))
    )
    (net (code "60") (name "Net-(U7-ZQ)") (class "Default")
      (node (ref "R31") (pin "2") (pinfunction "2_2") (pintype "passive"))
      (node (ref "U7") (pin "L8") (pinfunction "ZQ_L8") (pintype "passive"))
    )
  )
)
